# USB_interface.net
KiCad netlist of a schematic drawn in Altium Designer
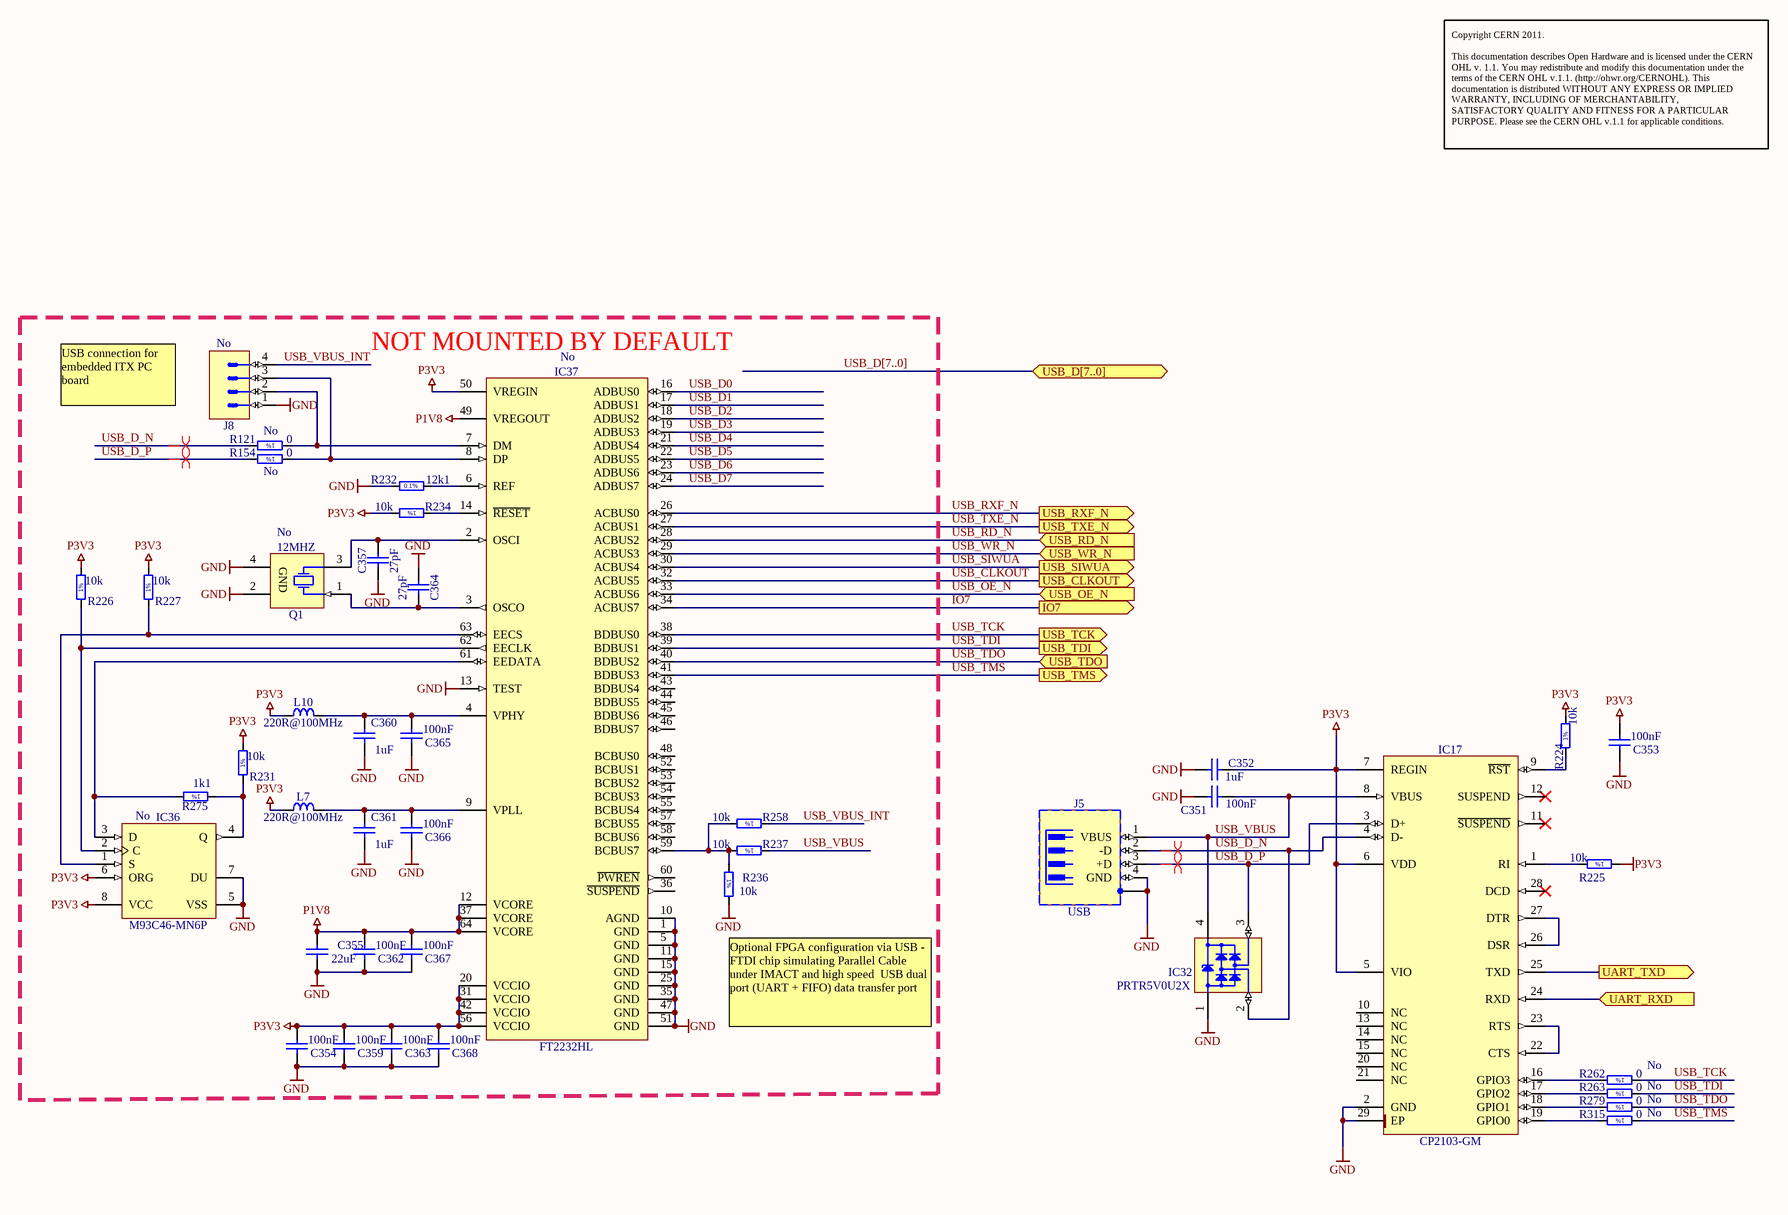
[diagram p0: USB_interface.SchDoc]

(export (version "E")
  (design (tool "Eeschema 10.0.6"))
  (components
    (comp (ref "C351")
      (value "100nF")
      (footprint "CAPC1005X55N")
      (description "Non-polarised capacitor")
      (fields
        (field (name "PART NUMBER") "CC0402_100NF_16V_10%_X7R")
        (field (name "VOLTAGE") "16V")
        (field (name "AUTHOR") "CERN DEM JLC")
      )
      (libsource (lib "Capacitors") (part "Capacitor - non polarized"))
    )
    (comp (ref "C352")
      (value "1uF")
      (footprint "CAPC1608X87N")
      (description "Non-polarised capacitor")
      (fields
        (field (name "PART NUMBER") "CC0603_1UF_16V_10%_X7R")
        (field (name "VOLTAGE") "16V")
        (field (name "AUTHOR") "CERN DEM JLC")
      )
      (libsource (lib "Capacitors") (part "Capacitor - non polarized"))
    )
    (comp (ref "C353")
      (value "100nF")
      (footprint "CAPC1005X55N")
      (description "Non-polarised capacitor")
      (fields
        (field (name "PART NUMBER") "CC0402_100NF_16V_10%_X7R")
        (field (name "VOLTAGE") "16V")
        (field (name "AUTHOR") "CERN DEM JLC")
      )
      (libsource (lib "Capacitors") (part "Capacitor - non polarized"))
    )
    (comp (ref "C354")
      (value "100nF")
      (footprint "CAPC1005X55N")
      (description "Non-polarised capacitor")
      (fields
        (field (name "PART NUMBER") "CC0402_100NF_16V_10%_X7R")
        (field (name "VOLTAGE") "16V")
        (field (name "AUTHOR") "CERN DEM JLC")
      )
      (libsource (lib "Capacitors") (part "Capacitor - non polarized"))
    )
    (comp (ref "C355")
      (value "22uF")
      (footprint "CAPC3216X180N")
      (description "Non-polarised capacitor")
      (fields
        (field (name "PART NUMBER") "CC1206_22UF_10V_10%_X7R")
        (field (name "VOLTAGE") "10V")
        (field (name "AUTHOR") "CERN DEM JLC")
      )
      (libsource (lib "Capacitors") (part "Capacitor - non polarized"))
    )
    (comp (ref "C357")
      (value "27pF")
      (footprint "CAPC1608X87N")
      (description "Non-polarised capacitor")
      (fields
        (field (name "PART NUMBER") "CC0603_27PF_50V_5%_NP0")
        (field (name "VOLTAGE") "50V")
        (field (name "AUTHOR") "CERN DEM JLC")
      )
      (libsource (lib "Capacitors") (part "Capacitor - non polarized"))
    )
    (comp (ref "C359")
      (value "100nF")
      (footprint "CAPC1005X55N")
      (description "Non-polarised capacitor")
      (fields
        (field (name "PART NUMBER") "CC0402_100NF_16V_10%_X7R")
        (field (name "VOLTAGE") "16V")
        (field (name "AUTHOR") "CERN DEM JLC")
      )
      (libsource (lib "Capacitors") (part "Capacitor - non polarized"))
    )
    (comp (ref "C360")
      (value "1uF")
      (footprint "CAPC1608X87N")
      (description "Non-polarised capacitor")
      (fields
        (field (name "PART NUMBER") "CC0603_1UF_16V_10%_X7R")
        (field (name "VOLTAGE") "16V")
        (field (name "AUTHOR") "CERN DEM JLC")
      )
      (libsource (lib "Capacitors") (part "Capacitor - non polarized"))
    )
    (comp (ref "C361")
      (value "1uF")
      (footprint "CAPC1608X87N")
      (description "Non-polarised capacitor")
      (fields
        (field (name "PART NUMBER") "CC0603_1UF_16V_10%_X7R")
        (field (name "VOLTAGE") "16V")
        (field (name "AUTHOR") "CERN DEM JLC")
      )
      (libsource (lib "Capacitors") (part "Capacitor - non polarized"))
    )
    (comp (ref "C362")
      (value "100nF")
      (footprint "CAPC1005X55N")
      (description "Non-polarised capacitor")
      (fields
        (field (name "PART NUMBER") "CC0402_100NF_16V_10%_X7R")
        (field (name "VOLTAGE") "16V")
        (field (name "AUTHOR") "CERN DEM JLC")
      )
      (libsource (lib "Capacitors") (part "Capacitor - non polarized"))
    )
    (comp (ref "C363")
      (value "100nF")
      (footprint "CAPC1005X55N")
      (description "Non-polarised capacitor")
      (fields
        (field (name "PART NUMBER") "CC0402_100NF_16V_10%_X7R")
        (field (name "VOLTAGE") "16V")
        (field (name "AUTHOR") "CERN DEM JLC")
      )
      (libsource (lib "Capacitors") (part "Capacitor - non polarized"))
    )
    (comp (ref "C364")
      (value "27pF")
      (footprint "CAPC1608X87N")
      (description "Non-polarised capacitor")
      (fields
        (field (name "PART NUMBER") "CC0603_27PF_50V_5%_NP0")
        (field (name "VOLTAGE") "50V")
        (field (name "AUTHOR") "CERN DEM JLC")
      )
      (libsource (lib "Capacitors") (part "Capacitor - non polarized"))
    )
    (comp (ref "C365")
      (value "100nF")
      (footprint "CAPC1005X55N")
      (description "Non-polarised capacitor")
      (fields
        (field (name "PART NUMBER") "CC0402_100NF_16V_10%_X7R")
        (field (name "VOLTAGE") "16V")
        (field (name "AUTHOR") "CERN DEM JLC")
      )
      (libsource (lib "Capacitors") (part "Capacitor - non polarized"))
    )
    (comp (ref "C366")
      (value "100nF")
      (footprint "CAPC1005X55N")
      (description "Non-polarised capacitor")
      (fields
        (field (name "PART NUMBER") "CC0402_100NF_16V_10%_X7R")
        (field (name "VOLTAGE") "16V")
        (field (name "AUTHOR") "CERN DEM JLC")
      )
      (libsource (lib "Capacitors") (part "Capacitor - non polarized"))
    )
    (comp (ref "C367")
      (value "100nF")
      (footprint "CAPC1005X55N")
      (description "Non-polarised capacitor")
      (fields
        (field (name "PART NUMBER") "CC0402_100NF_16V_10%_X7R")
        (field (name "VOLTAGE") "16V")
        (field (name "AUTHOR") "CERN DEM JLC")
      )
      (libsource (lib "Capacitors") (part "Capacitor - non polarized"))
    )
    (comp (ref "C368")
      (value "100nF")
      (footprint "CAPC1005X55N")
      (description "Non-polarised capacitor")
      (fields
        (field (name "PART NUMBER") "CC0402_100NF_16V_10%_X7R")
        (field (name "VOLTAGE") "16V")
        (field (name "AUTHOR") "CERN DEM JLC")
      )
      (libsource (lib "Capacitors") (part "Capacitor - non polarized"))
    )
    (comp (ref "IC17")
      (value "CP2103-GM")
      (footprint "QFN50P500X500X100-29N-S335")
      (description "Single-Chip USB to UART Bridge")
      (fields (field (name "MANUFACTURER") "SILICON LABS") (field (name "AUTHOR") "CERN DEM JLC"))
      (libsource (lib "ICs And Semiconductors") (part "CP2103-GM"))
    )
    (comp (ref "IC32")
      (value "PRTR5V0U2X")
      (footprint "SOT190P230X110-4N")
      (description "Ultra Low Capacitance Double Rail-to-Rail ESD Protection Diode")
      (fields
        (field (name "VOLTAGE") "5.5V")
        (field (name "MANUFACTURER") "PHILIPS NXP")
        (field (name "AUTHOR") "CERN DEM JLC")
      )
      (libsource (lib "ICs And Semiconductors") (part "PRTR5V0U2X"))
    )
    (comp (ref "IC36")
      (value "M93C46-MN6P")
      (footprint "SOIC127P600X175-8N")
      (description "1Kb (x8/x16) Serial Microwire Bus EEPROM")
      (fields
        (field (name "MANUFACTURER") "ST MICROELECTRONICS")
        (field (name "MOUNTED") "No")
        (field (name "AUTHOR") "CERN DEM JLC")
      )
      (libsource (lib "ICs And Semiconductors") (part "M93C46-MN"))
    )
    (comp (ref "IC37")
      (value "FT2232HL")
      (footprint "QFP50P1200X1200X160-64N")
      (description "Dual High Speed USB to Multipurpose UART/FIFO IC")
      (fields
        (field (name "MANUFACTURER") "FUTURE TECHNOLOGY DEVICES INTERNATIONAL (FTDI)")
        (field (name "MOUNTED") "No")
        (field (name "AUTHOR") "CERN DEM JLC")
      )
      (libsource (lib "ICs And Semiconductors") (part "FT2232H"))
    )
    (comp (ref "J5")
      (value "USB")
      (footprint "TYCO_292304-1")
      (description "4 Pin + 1 Shield USB Receptacle")
      (fields
        (field (name "PART NUMBER") "TYCO_292304-1")
        (field (name "MANUFACTURER") "TYCO ELECTRONICS")
        (field (name "AUTHOR") "CERN DEM JLC")
      )
      (libsource (lib "Connectors") (part "Connector USB 4 Pin + 1Shield"))
    )
    (comp (ref "J8")
      (value "KK®")
      (footprint "MOLEX_22-04-1041")
      (description "Connector 4 Male")
      (fields
        (field (name "PART NUMBER") "MOLEX_22-04-1041")
        (field (name "MOUNTED") "No")
        (field (name "MANUFACTURER") "MOLEX")
        (field (name "AUTHOR") "CERN DEM JLC")
      )
      (libsource (lib "Connectors") (part "Connector 4 Male"))
    )
    (comp (ref "L7")
      (value "220R@100MHz")
      (footprint "INDC2012X105N")
      (description "Inductor")
      (fields
        (field (name "PART NUMBER") "IND0805_MURATA_BLM21PG221SN1D")
        (field (name "POWER") "2A")
        (field (name "AUTHOR") "CERN DEM JLC")
      )
      (libsource (lib "Inductors & Transformers") (part "Inductor"))
    )
    (comp (ref "L10")
      (value "220R@100MHz")
      (footprint "INDC2012X105N")
      (description "Inductor")
      (fields
        (field (name "PART NUMBER") "IND0805_MURATA_BLM21PG221SN1D")
        (field (name "POWER") "2A")
        (field (name "AUTHOR") "CERN DEM JLC")
      )
      (libsource (lib "Inductors & Transformers") (part "Inductor"))
    )
    (comp (ref "Q1")
      (value "12MHZ")
      (footprint "XTAL_ABRACON_ABM3B")
      (description "Crystal 4 pins 1=XTAL Control 2=GND3=XTAL 4=GND")
      (fields
        (field (name "PART NUMBER") "XTAL_12MHZ_ABRACON_ABM3B-12.000MHZ-B2-T")
        (field (name "MANUFACTURER") "ABRACON")
        (field (name "MOUNTED") "No")
        (field (name "AUTHOR") "CERN DEM JLC")
      )
      (libsource (lib "ICs And Semiconductors") (part "Quartz Crystal 1X 2GND 3X 4GND"))
    )
    (comp (ref "R121")
      (value "0")
      (footprint "RESC1608X55N")
      (description "Resistor - 1%")
      (fields
        (field (name "PART NUMBER") "R0603_0R_JUMPER")
        (field (name "MANUFACTURER") "GENERIC")
        (field (name "MOUNTED") "No")
        (field (name "AUTHOR") "CERN DEM JLC")
      )
      (libsource (lib "Resistors") (part "Resistor - 1%"))
    )
    (comp (ref "R154")
      (value "0")
      (footprint "RESC1608X55N")
      (description "Resistor - 1%")
      (fields
        (field (name "PART NUMBER") "R0603_0R_JUMPER")
        (field (name "MANUFACTURER") "GENERIC")
        (field (name "MOUNTED") "No")
        (field (name "AUTHOR") "CERN DEM JLC")
      )
      (libsource (lib "Resistors") (part "Resistor - 1%"))
    )
    (comp (ref "R224")
      (value "10k")
      (footprint "RESC1608X55N")
      (description "Resistor - 1%")
      (fields
        (field (name "PART NUMBER") "R0603_10K_1%_0.1W_100PPM")
        (field (name "POWER") "0.1W")
        (field (name "AUTHOR") "CERN DEM JLC")
      )
      (libsource (lib "Resistors") (part "Resistor - 1%"))
    )
    (comp (ref "R225")
      (value "10k")
      (footprint "RESC1608X55N")
      (description "Resistor - 1%")
      (fields
        (field (name "PART NUMBER") "R0603_10K_1%_0.1W_100PPM")
        (field (name "POWER") "0.1W")
        (field (name "AUTHOR") "CERN DEM JLC")
      )
      (libsource (lib "Resistors") (part "Resistor - 1%"))
    )
    (comp (ref "R226")
      (value "10k")
      (footprint "RESC1608X55N")
      (description "Resistor - 1%")
      (fields
        (field (name "PART NUMBER") "R0603_10K_1%_0.1W_100PPM")
        (field (name "POWER") "0.1W")
        (field (name "AUTHOR") "CERN DEM JLC")
      )
      (libsource (lib "Resistors") (part "Resistor - 1%"))
    )
    (comp (ref "R227")
      (value "10k")
      (footprint "RESC1608X55N")
      (description "Resistor - 1%")
      (fields
        (field (name "PART NUMBER") "R0603_10K_1%_0.1W_100PPM")
        (field (name "POWER") "0.1W")
        (field (name "AUTHOR") "CERN DEM JLC")
      )
      (libsource (lib "Resistors") (part "Resistor - 1%"))
    )
    (comp (ref "R231")
      (value "10k")
      (footprint "RESC1608X55N")
      (description "Resistor - 1%")
      (fields
        (field (name "PART NUMBER") "R0603_10K_1%_0.1W_100PPM")
        (field (name "POWER") "0.1W")
        (field (name "AUTHOR") "CERN DEM JLC")
      )
      (libsource (lib "Resistors") (part "Resistor - 1%"))
    )
    (comp (ref "R232")
      (value "12k1")
      (footprint "RESC1608X55N")
      (description "Resistor - 0.1%")
      (fields
        (field (name "PART NUMBER") "R0603_12K1_0.1%_0.063W_10PPM")
        (field (name "POWER") "0.063W")
        (field (name "AUTHOR") "CERN DEM JLC")
      )
      (libsource (lib "Resistors") (part "Resistor - 0.1%"))
    )
    (comp (ref "R234")
      (value "10k")
      (footprint "RESC1608X55N")
      (description "Resistor - 1%")
      (fields
        (field (name "PART NUMBER") "R0603_10K_1%_0.1W_100PPM")
        (field (name "POWER") "0.1W")
        (field (name "AUTHOR") "CERN DEM JLC")
      )
      (libsource (lib "Resistors") (part "Resistor - 1%"))
    )
    (comp (ref "R236")
      (value "10k")
      (footprint "RESC1608X55N")
      (description "Resistor - 1%")
      (fields
        (field (name "PART NUMBER") "R0603_10K_1%_0.1W_100PPM")
        (field (name "POWER") "0.1W")
        (field (name "AUTHOR") "CERN DEM JLC")
      )
      (libsource (lib "Resistors") (part "Resistor - 1%"))
    )
    (comp (ref "R237")
      (value "10k")
      (footprint "RESC1608X55N")
      (description "Resistor - 1%")
      (fields
        (field (name "PART NUMBER") "R0603_10K_1%_0.1W_100PPM")
        (field (name "POWER") "0.1W")
        (field (name "AUTHOR") "CERN DEM JLC")
      )
      (libsource (lib "Resistors") (part "Resistor - 1%"))
    )
    (comp (ref "R258")
      (value "10k")
      (footprint "RESC1608X55N")
      (description "Resistor - 1%")
      (fields
        (field (name "PART NUMBER") "R0603_10K_1%_0.1W_100PPM")
        (field (name "POWER") "0.1W")
        (field (name "AUTHOR") "CERN DEM JLC")
      )
      (libsource (lib "Resistors") (part "Resistor - 1%"))
    )
    (comp (ref "R262")
      (value "0")
      (footprint "RESC1608X55N")
      (description "Resistor - 1%")
      (fields
        (field (name "PART NUMBER") "R0603_0R_JUMPER")
        (field (name "MANUFACTURER") "GENERIC")
        (field (name "MOUNTED") "No")
        (field (name "AUTHOR") "CERN DEM JLC")
      )
      (libsource (lib "Resistors") (part "Resistor - 1%"))
    )
    (comp (ref "R263")
      (value "0")
      (footprint "RESC1608X55N")
      (description "Resistor - 1%")
      (fields
        (field (name "PART NUMBER") "R0603_0R_JUMPER")
        (field (name "MANUFACTURER") "GENERIC")
        (field (name "MOUNTED") "No")
        (field (name "AUTHOR") "CERN DEM JLC")
      )
      (libsource (lib "Resistors") (part "Resistor - 1%"))
    )
    (comp (ref "R275")
      (value "1k1")
      (footprint "RESC1608X55N")
      (description "Resistor - 1%")
      (fields
        (field (name "PART NUMBER") "R0603_1K1_1%_0.1W_100PPM")
        (field (name "POWER") "0.1W")
        (field (name "AUTHOR") "CERN DEM JLC")
      )
      (libsource (lib "Resistors") (part "Resistor - 1%"))
    )
    (comp (ref "R279")
      (value "0")
      (footprint "RESC1608X55N")
      (description "Resistor - 1%")
      (fields
        (field (name "PART NUMBER") "R0603_0R_JUMPER")
        (field (name "MANUFACTURER") "GENERIC")
        (field (name "MOUNTED") "No")
        (field (name "AUTHOR") "CERN DEM JLC")
      )
      (libsource (lib "Resistors") (part "Resistor - 1%"))
    )
    (comp (ref "R315")
      (value "0")
      (footprint "RESC1608X55N")
      (description "Resistor - 1%")
      (fields
        (field (name "PART NUMBER") "R0603_0R_JUMPER")
        (field (name "MANUFACTURER") "GENERIC")
        (field (name "MOUNTED") "No")
        (field (name "AUTHOR") "CERN DEM JLC")
      )
      (libsource (lib "Resistors") (part "Resistor - 1%"))
    )
  )
  (nets
    (net (code "1") (name "/IO7") (class "Default")
      (node (ref "IC37") (pin "34") (pinfunction "ACBUS7_34") (pintype "bidirectional"))
    )
    (net (code "2") (name "/UART_RXD") (class "Default")
      (node (ref "IC17") (pin "24") (pinfunction "RXD_24") (pintype "input"))
    )
    (net (code "3") (name "/UART_TXD") (class "Default")
      (node (ref "IC17") (pin "25") (pinfunction "TXD_25") (pintype "output"))
    )
    (net (code "4") (name "/USB_CLKOUT") (class "Default")
      (node (ref "IC37") (pin "32") (pinfunction "ACBUS5_32") (pintype "bidirectional"))
    )
    (net (code "5") (name "/USB_D0") (class "Default")
      (node (ref "IC37") (pin "16") (pinfunction "ADBUS0_16") (pintype "bidirectional"))
    )
    (net (code "6") (name "/USB_D1") (class "Default")
      (node (ref "IC37") (pin "17") (pinfunction "ADBUS1_17") (pintype "bidirectional"))
    )
    (net (code "7") (name "/USB_D2") (class "Default")
      (node (ref "IC37") (pin "18") (pinfunction "ADBUS2_18") (pintype "bidirectional"))
    )
    (net (code "8") (name "/USB_D3") (class "Default")
      (node (ref "IC37") (pin "19") (pinfunction "ADBUS3_19") (pintype "bidirectional"))
    )
    (net (code "9") (name "/USB_D4") (class "Default")
      (node (ref "IC37") (pin "21") (pinfunction "ADBUS4_21") (pintype "bidirectional"))
    )
    (net (code "10") (name "/USB_D5") (class "Default")
      (node (ref "IC37") (pin "22") (pinfunction "ADBUS5_22") (pintype "bidirectional"))
    )
    (net (code "11") (name "/USB_D6") (class "Default")
      (node (ref "IC37") (pin "23") (pinfunction "ADBUS6_23") (pintype "bidirectional"))
    )
    (net (code "12") (name "/USB_D7") (class "Default")
      (node (ref "IC37") (pin "24") (pinfunction "ADBUS7_24") (pintype "bidirectional"))
    )
    (net (code "14") (name "/USB_D_N") (class "Default")
      (node (ref "IC17") (pin "4") (pinfunction "D-_4") (pintype "bidirectional"))
      (node (ref "IC32") (pin "2") (pinfunction "I/O1_2") (pintype "bidirectional"))
      (node (ref "J5") (pin "2") (pinfunction "-D_2") (pintype "bidirectional"))
      (node (ref "R121") (pin "2") (pinfunction "2_2") (pintype "passive"))
    )
    (net (code "15") (name "/USB_D_P") (class "Default")
      (node (ref "IC17") (pin "3") (pinfunction "D+_3") (pintype "bidirectional"))
      (node (ref "IC32") (pin "3") (pinfunction "I/O2_3") (pintype "bidirectional"))
      (node (ref "J5") (pin "3") (pinfunction "+D_3") (pintype "bidirectional"))
      (node (ref "R154") (pin "2") (pinfunction "2_2") (pintype "passive"))
    )
    (net (code "16") (name "/USB_OE_N") (class "Default")
      (node (ref "IC37") (pin "33") (pinfunction "ACBUS6_33") (pintype "bidirectional"))
    )
    (net (code "17") (name "/USB_RD_N") (class "Default")
      (node (ref "IC37") (pin "28") (pinfunction "ACBUS2_28") (pintype "bidirectional"))
    )
    (net (code "18") (name "/USB_RXF_N") (class "Default")
      (node (ref "IC37") (pin "26") (pinfunction "ACBUS0_26") (pintype "bidirectional"))
    )
    (net (code "19") (name "/USB_SIWUA") (class "Default")
      (node (ref "IC37") (pin "30") (pinfunction "ACBUS4_30") (pintype "bidirectional"))
    )
    (net (code "20") (name "/USB_TCK") (class "Default")
      (node (ref "IC37") (pin "38") (pinfunction "BDBUS0_38") (pintype "bidirectional"))
      (node (ref "R262") (pin "1") (pinfunction "1_1") (pintype "passive"))
    )
    (net (code "21") (name "/USB_TDI") (class "Default")
      (node (ref "IC37") (pin "39") (pinfunction "BDBUS1_39") (pintype "bidirectional"))
      (node (ref "R263") (pin "1") (pinfunction "1_1") (pintype "passive"))
    )
    (net (code "22") (name "/USB_TDO") (class "Default")
      (node (ref "IC37") (pin "40") (pinfunction "BDBUS2_40") (pintype "bidirectional"))
      (node (ref "R279") (pin "1") (pinfunction "1_1") (pintype "passive"))
    )
    (net (code "23") (name "/USB_TMS") (class "Default")
      (node (ref "IC37") (pin "41") (pinfunction "BDBUS3_41") (pintype "bidirectional"))
      (node (ref "R315") (pin "1") (pinfunction "1_1") (pintype "passive"))
    )
    (net (code "24") (name "/USB_TXE_N") (class "Default")
      (node (ref "IC37") (pin "27") (pinfunction "ACBUS1_27") (pintype "bidirectional"))
    )
    (net (code "25") (name "/USB_VBUS") (class "Default")
      (node (ref "C351") (pin "1") (pinfunction "1_1") (pintype "passive"))
      (node (ref "IC17") (pin "8") (pinfunction "VBUS_8") (pintype "input"))
      (node (ref "IC32") (pin "4") (pinfunction "VCC_4") (pintype "power_in"))
      (node (ref "J5") (pin "1") (pinfunction "VBUS_1") (pintype "bidirectional"))
      (node (ref "R237") (pin "1") (pinfunction "1_1") (pintype "passive"))
    )
    (net (code "26") (name "/USB_VBUS_INT") (class "Default")
      (node (ref "J8") (pin "4") (pinfunction "4_4") (pintype "bidirectional"))
      (node (ref "R258") (pin "1") (pinfunction "1_1") (pintype "passive"))
    )
    (net (code "27") (name "/USB_WR_N") (class "Default")
      (node (ref "IC37") (pin "29") (pinfunction "ACBUS3_29") (pintype "bidirectional"))
    )
    (net (code "28") (name "GND") (class "Default")
      (node (ref "C351") (pin "2") (pinfunction "2_2") (pintype "passive"))
      (node (ref "C352") (pin "2") (pinfunction "2_2") (pintype "passive"))
      (node (ref "C353") (pin "2") (pinfunction "2_2") (pintype "passive"))
      (node (ref "C354") (pin "2") (pinfunction "2_2") (pintype "passive"))
      (node (ref "C355") (pin "1") (pinfunction "1_1") (pintype "passive"))
      (node (ref "C357") (pin "1") (pinfunction "1_1") (pintype "passive"))
      (node (ref "C359") (pin "2") (pinfunction "2_2") (pintype "passive"))
      (node (ref "C360") (pin "1") (pinfunction "1_1") (pintype "passive"))
      (node (ref "C361") (pin "1") (pinfunction "1_1") (pintype "passive"))
      (node (ref "C362") (pin "2") (pinfunction "2_2") (pintype "passive"))
      (node (ref "C363") (pin "2") (pinfunction "2_2") (pintype "passive"))
      (node (ref "C364") (pin "1") (pinfunction "1_1") (pintype "passive"))
      (node (ref "C365") (pin "2") (pinfunction "2_2") (pintype "passive"))
      (node (ref "C366") (pin "2") (pinfunction "2_2") (pintype "passive"))
      (node (ref "C367") (pin "2") (pinfunction "2_2") (pintype "passive"))
      (node (ref "C368") (pin "2") (pinfunction "2_2") (pintype "passive"))
      (node (ref "IC17") (pin "2") (pinfunction "GND_2") (pintype "power_in"))
      (node (ref "IC17") (pin "29") (pinfunction "EP_29") (pintype "power_in"))
      (node (ref "IC32") (pin "1") (pinfunction "GND_1") (pintype "power_in"))
      (node (ref "IC36") (pin "5") (pinfunction "VSS_5") (pintype "power_in"))
      (node (ref "IC36") (pin "7") (pinfunction "DU_7") (pintype "passive"))
      (node (ref "IC37") (pin "1") (pinfunction "GND_1") (pintype "power_in"))
      (node (ref "IC37") (pin "10") (pinfunction "AGND_10") (pintype "power_in"))
      (node (ref "IC37") (pin "11") (pinfunction "GND_11") (pintype "power_in"))
      (node (ref "IC37") (pin "13") (pinfunction "TEST_13") (pintype "input"))
      (node (ref "IC37") (pin "15") (pinfunction "GND_15") (pintype "power_in"))
      (node (ref "IC37") (pin "25") (pinfunction "GND_25") (pintype "power_in"))
      (node (ref "IC37") (pin "35") (pinfunction "GND_35") (pintype "power_in"))
      (node (ref "IC37") (pin "47") (pinfunction "GND_47") (pintype "power_in"))
      (node (ref "IC37") (pin "5") (pinfunction "GND_5") (pintype "power_in"))
      (node (ref "IC37") (pin "51") (pinfunction "GND_51") (pintype "power_in"))
      (node (ref "J5") (pin "4") (pinfunction "GND_4") (pintype "bidirectional"))
      (node (ref "J5") (pin "5") (pinfunction "SH_5") (pintype "power_in"))
      (node (ref "J8") (pin "1") (pinfunction "1_1") (pintype "bidirectional"))
      (node (ref "Q1") (pin "2") (pinfunction "GND_2") (pintype "power_in"))
      (node (ref "Q1") (pin "4") (pinfunction "GND_4") (pintype "power_in"))
      (node (ref "R232") (pin "1") (pinfunction "1_1") (pintype "passive"))
      (node (ref "R236") (pin "2") (pinfunction "2_2") (pintype "passive"))
    )
    (net (code "29") (name "Net-(IC17-CTS)") (class "Default")
      (node (ref "IC17") (pin "22") (pinfunction "CTS_22") (pintype "input"))
      (node (ref "IC17") (pin "23") (pinfunction "RTS_23") (pintype "output"))
    )
    (net (code "30") (name "Net-(IC17-DSR)") (class "Default")
      (node (ref "IC17") (pin "26") (pinfunction "DSR_26") (pintype "input"))
      (node (ref "IC17") (pin "27") (pinfunction "DTR_27") (pintype "output"))
    )
    (net (code "31") (name "Net-(IC17-GPIO0)") (class "Default")
      (node (ref "IC17") (pin "19") (pinfunction "GPIO0_19") (pintype "bidirectional"))
      (node (ref "R315") (pin "2") (pinfunction "2_2") (pintype "passive"))
    )
    (net (code "32") (name "Net-(IC17-GPIO1)") (class "Default")
      (node (ref "IC17") (pin "18") (pinfunction "GPIO1_18") (pintype "bidirectional"))
      (node (ref "R279") (pin "2") (pinfunction "2_2") (pintype "passive"))
    )
    (net (code "33") (name "Net-(IC17-GPIO2)") (class "Default")
      (node (ref "IC17") (pin "17") (pinfunction "GPIO2_17") (pintype "bidirectional"))
      (node (ref "R263") (pin "2") (pinfunction "2_2") (pintype "passive"))
    )
    (net (code "34") (name "Net-(IC17-GPIO3)") (class "Default")
      (node (ref "IC17") (pin "16") (pinfunction "GPIO3_16") (pintype "bidirectional"))
      (node (ref "R262") (pin "2") (pinfunction "2_2") (pintype "passive"))
    )
    (net (code "35") (name "Net-(IC17-RI)") (class "Default")
      (node (ref "IC17") (pin "1") (pinfunction "RI_1") (pintype "input"))
      (node (ref "R225") (pin "2") (pinfunction "2_2") (pintype "passive"))
    )
    (net (code "36") (name "Net-(IC17-~{RST})") (class "Default")
      (node (ref "IC17") (pin "9") (pinfunction "~{RST}_9") (pintype "bidirectional"))
      (node (ref "R224") (pin "1") (pinfunction "1_1") (pintype "passive"))
    )
    (net (code "37") (name "Net-(IC36-C)") (class "Default")
      (node (ref "IC36") (pin "2") (pinfunction "C_2") (pintype "input"))
      (node (ref "IC37") (pin "62") (pinfunction "EECLK_62") (pintype "output"))
      (node (ref "R226") (pin "1") (pinfunction "1_1") (pintype "passive"))
    )
    (net (code "38") (name "Net-(IC36-D)") (class "Default")
      (node (ref "IC36") (pin "3") (pinfunction "D_3") (pintype "input"))
      (node (ref "IC37") (pin "61") (pinfunction "EEDATA_61") (pintype "bidirectional"))
      (node (ref "R275") (pin "2") (pinfunction "2_2") (pintype "passive"))
    )
    (net (code "39") (name "Net-(IC36-Q)") (class "Default")
      (node (ref "IC36") (pin "4") (pinfunction "Q_4") (pintype "output"))
      (node (ref "R231") (pin "1") (pinfunction "1_1") (pintype "passive"))
      (node (ref "R275") (pin "1") (pinfunction "1_1") (pintype "passive"))
    )
    (net (code "40") (name "Net-(IC36-S)") (class "Default")
      (node (ref "IC36") (pin "1") (pinfunction "S_1") (pintype "input"))
      (node (ref "IC37") (pin "63") (pinfunction "EECS_63") (pintype "bidirectional"))
      (node (ref "R227") (pin "1") (pinfunction "1_1") (pintype "passive"))
    )
    (net (code "41") (name "Net-(IC37-BCBUS7)") (class "Default")
      (node (ref "IC37") (pin "59") (pinfunction "BCBUS7_59") (pintype "bidirectional"))
      (node (ref "R236") (pin "1") (pinfunction "1_1") (pintype "passive"))
      (node (ref "R237") (pin "2") (pinfunction "2_2") (pintype "passive"))
      (node (ref "R258") (pin "2") (pinfunction "2_2") (pintype "passive"))
    )
    (net (code "42") (name "Net-(IC37-DM)") (class "Default")
      (node (ref "IC37") (pin "7") (pinfunction "DM_7") (pintype "input"))
      (node (ref "J8") (pin "2") (pinfunction "2_2") (pintype "bidirectional"))
      (node (ref "R121") (pin "1") (pinfunction "1_1") (pintype "passive"))
    )
    (net (code "43") (name "Net-(IC37-DP)") (class "Default")
      (node (ref "IC37") (pin "8") (pinfunction "DP_8") (pintype "input"))
      (node (ref "J8") (pin "3") (pinfunction "3_3") (pintype "bidirectional"))
      (node (ref "R154") (pin "1") (pinfunction "1_1") (pintype "passive"))
    )
    (net (code "44") (name "Net-(IC37-OSCI)") (class "Default")
      (node (ref "C357") (pin "2") (pinfunction "2_2") (pintype "passive"))
      (node (ref "IC37") (pin "2") (pinfunction "OSCI_2") (pintype "input"))
      (node (ref "Q1") (pin "3") (pinfunction "X_3") (pintype "power_in"))
    )
    (net (code "45") (name "Net-(IC37-OSCO)") (class "Default")
      (node (ref "C364") (pin "2") (pinfunction "2_2") (pintype "passive"))
      (node (ref "IC37") (pin "3") (pinfunction "OSCO_3") (pintype "output"))
      (node (ref "Q1") (pin "1") (pinfunction "X_1") (pintype "input"))
    )
    (net (code "46") (name "Net-(IC37-REF)") (class "Default")
      (node (ref "IC37") (pin "6") (pinfunction "REF_6") (pintype "input"))
      (node (ref "R232") (pin "2") (pinfunction "2_2") (pintype "passive"))
    )
    (net (code "47") (name "Net-(IC37-VPHY)") (class "Default")
      (node (ref "C360") (pin "2") (pinfunction "2_2") (pintype "passive"))
      (node (ref "C365") (pin "1") (pinfunction "1_1") (pintype "passive"))
      (node (ref "IC37") (pin "4") (pinfunction "VPHY_4") (pintype "power_in"))
      (node (ref "L10") (pin "2") (pinfunction "2_2") (pintype "passive"))
    )
    (net (code "48") (name "Net-(IC37-VPLL)") (class "Default")
      (node (ref "C361") (pin "2") (pinfunction "2_2") (pintype "passive"))
      (node (ref "C366") (pin "1") (pinfunction "1_1") (pintype "passive"))
      (node (ref "IC37") (pin "9") (pinfunction "VPLL_9") (pintype "power_in"))
      (node (ref "L7") (pin "2") (pinfunction "2_2") (pintype "passive"))
    )
    (net (code "49") (name "Net-(IC37-~{RESET})") (class "Default")
      (node (ref "IC37") (pin "14") (pinfunction "~{RESET}_14") (pintype "input"))
      (node (ref "R234") (pin "1") (pinfunction "1_1") (pintype "passive"))
    )
    (net (code "50") (name "P1V8") (class "Default")
      (node (ref "C355") (pin "2") (pinfunction "2_2") (pintype "passive"))
      (node (ref "C362") (pin "1") (pinfunction "1_1") (pintype "passive"))
      (node (ref "C367") (pin "1") (pinfunction "1_1") (pintype "passive"))
      (node (ref "IC37") (pin "12") (pinfunction "VCORE_12") (pintype "power_in"))
      (node (ref "IC37") (pin "37") (pinfunction "VCORE_37") (pintype "power_in"))
      (node (ref "IC37") (pin "49") (pinfunction "VREGOUT_49") (pintype "power_in"))
      (node (ref "IC37") (pin "64") (pinfunction "VCORE_64") (pintype "power_in"))
    )
    (net (code "51") (name "P3V3") (class "Default")
      (node (ref "C352") (pin "1") (pinfunction "1_1") (pintype "passive"))
      (node (ref "C353") (pin "1") (pinfunction "1_1") (pintype "passive"))
      (node (ref "C354") (pin "1") (pinfunction "1_1") (pintype "passive"))
      (node (ref "C359") (pin "1") (pinfunction "1_1") (pintype "passive"))
      (node (ref "C363") (pin "1") (pinfunction "1_1") (pintype "passive"))
      (node (ref "C368") (pin "1") (pinfunction "1_1") (pintype "passive"))
      (node (ref "IC17") (pin "5") (pinfunction "VIO_5") (pintype "power_in"))
      (node (ref "IC17") (pin "6") (pinfunction "VDD_6") (pintype "power_in"))
      (node (ref "IC17") (pin "7") (pinfunction "REGIN_7") (pintype "power_in"))
      (node (ref "IC36") (pin "6") (pinfunction "ORG_6") (pintype "input"))
      (node (ref "IC36") (pin "8") (pinfunction "VCC_8") (pintype "power_in"))
      (node (ref "IC37") (pin "20") (pinfunction "VCCIO_20") (pintype "power_in"))
      (node (ref "IC37") (pin "31") (pinfunction "VCCIO_31") (pintype "power_in"))
      (node (ref "IC37") (pin "42") (pinfunction "VCCIO_42") (pintype "power_in"))
      (node (ref "IC37") (pin "50") (pinfunction "VREGIN_50") (pintype "power_in"))
      (node (ref "IC37") (pin "56") (pinfunction "VCCIO_56") (pintype "power_in"))
      (node (ref "L10") (pin "1") (pinfunction "1_1") (pintype "passive"))
      (node (ref "L7") (pin "1") (pinfunction "1_1") (pintype "passive"))
      (node (ref "R224") (pin "2") (pinfunction "2_2") (pintype "passive"))
      (node (ref "R225") (pin "1") (pinfunction "1_1") (pintype "passive"))
      (node (ref "R226") (pin "2") (pinfunction "2_2") (pintype "passive"))
      (node (ref "R227") (pin "2") (pinfunction "2_2") (pintype "passive"))
      (node (ref "R231") (pin "2") (pinfunction "2_2") (pintype "passive"))
      (node (ref "R234") (pin "2") (pinfunction "2_2") (pintype "passive"))
    )
    (net (code "52") (name "unconnected-(IC17-DCD-Pad28)") (class "Default")
      (node (ref "IC17") (pin "28") (pinfunction "DCD_28") (pintype "input+no_connect"))
    )
    (net (code "53") (name "unconnected-(IC17-NC-Pad10)") (class "Default")
      (node (ref "IC17") (pin "10") (pinfunction "NC_10") (pintype "passive"))
    )
    (net (code "54") (name "unconnected-(IC17-NC-Pad13)") (class "Default")
      (node (ref "IC17") (pin "13") (pinfunction "NC_13") (pintype "passive"))
    )
    (net (code "55") (name "unconnected-(IC17-NC-Pad14)") (class "Default")
      (node (ref "IC17") (pin "14") (pinfunction "NC_14") (pintype "passive"))
    )
    (net (code "56") (name "unconnected-(IC17-NC-Pad15)") (class "Default")
      (node (ref "IC17") (pin "15") (pinfunction "NC_15") (pintype "passive"))
    )
    (net (code "57") (name "unconnected-(IC17-NC-Pad20)") (class "Default")
      (node (ref "IC17") (pin "20") (pinfunction "NC_20") (pintype "passive"))
    )
    (net (code "58") (name "unconnected-(IC17-NC-Pad21)") (class "Default")
      (node (ref "IC17") (pin "21") (pinfunction "NC_21") (pintype "passive"))
    )
    (net (code "59") (name "unconnected-(IC17-SUSPEND-Pad12)") (class "Default")
      (node (ref "IC17") (pin "12") (pinfunction "SUSPEND_12") (pintype "output+no_connect"))
    )
    (net (code "60") (name "unconnected-(IC17-~{SUSPEND}-Pad11)") (class "Default")
      (node (ref "IC17") (pin "11") (pinfunction "~{SUSPEND}_11") (pintype "output+no_connect"))
    )
    (net (code "61") (name "unconnected-(IC37-BCBUS0-Pad48)") (class "Default")
      (node (ref "IC37") (pin "48") (pinfunction "BCBUS0_48") (pintype "bidirectional"))
    )
    (net (code "62") (name "unconnected-(IC37-BCBUS1-Pad52)") (class "Default")
      (node (ref "IC37") (pin "52") (pinfunction "BCBUS1_52") (pintype "bidirectional"))
    )
    (net (code "63") (name "unconnected-(IC37-BCBUS2-Pad53)") (class "Default")
      (node (ref "IC37") (pin "53") (pinfunction "BCBUS2_53") (pintype "bidirectional"))
    )
    (net (code "64") (name "unconnected-(IC37-BCBUS3-Pad54)") (class "Default")
      (node (ref "IC37") (pin "54") (pinfunction "BCBUS3_54") (pintype "bidirectional"))
    )
    (net (code "65") (name "unconnected-(IC37-BCBUS4-Pad55)") (class "Default")
      (node (ref "IC37") (pin "55") (pinfunction "BCBUS4_55") (pintype "bidirectional"))
    )
    (net (code "66") (name "unconnected-(IC37-BCBUS5-Pad57)") (class "Default")
      (node (ref "IC37") (pin "57") (pinfunction "BCBUS5_57") (pintype "bidirectional"))
    )
    (net (code "67") (name "unconnected-(IC37-BCBUS6-Pad58)") (class "Default")
      (node (ref "IC37") (pin "58") (pinfunction "BCBUS6_58") (pintype "bidirectional"))
    )
    (net (code "68") (name "unconnected-(IC37-BDBUS4-Pad43)") (class "Default")
      (node (ref "IC37") (pin "43") (pinfunction "BDBUS4_43") (pintype "bidirectional"))
    )
    (net (code "69") (name "unconnected-(IC37-BDBUS5-Pad44)") (class "Default")
      (node (ref "IC37") (pin "44") (pinfunction "BDBUS5_44") (pintype "bidirectional"))
    )
    (net (code "70") (name "unconnected-(IC37-BDBUS6-Pad45)") (class "Default")
      (node (ref "IC37") (pin "45") (pinfunction "BDBUS6_45") (pintype "bidirectional"))
    )
    (net (code "71") (name "unconnected-(IC37-BDBUS7-Pad46)") (class "Default")
      (node (ref "IC37") (pin "46") (pinfunction "BDBUS7_46") (pintype "bidirectional"))
    )
    (net (code "72") (name "unconnected-(IC37-~{PWREN}-Pad60)") (class "Default")
      (node (ref "IC37") (pin "60") (pinfunction "~{PWREN}_60") (pintype "output"))
    )
    (net (code "73") (name "unconnected-(IC37-~{SUSPEND}-Pad36)") (class "Default")
      (node (ref "IC37") (pin "36") (pinfunction "~{SUSPEND}_36") (pintype "output"))
    )
  )
)
